# 4_shkb_downstream_power.net
KiCad netlist of a schematic drawn in Altium Designer
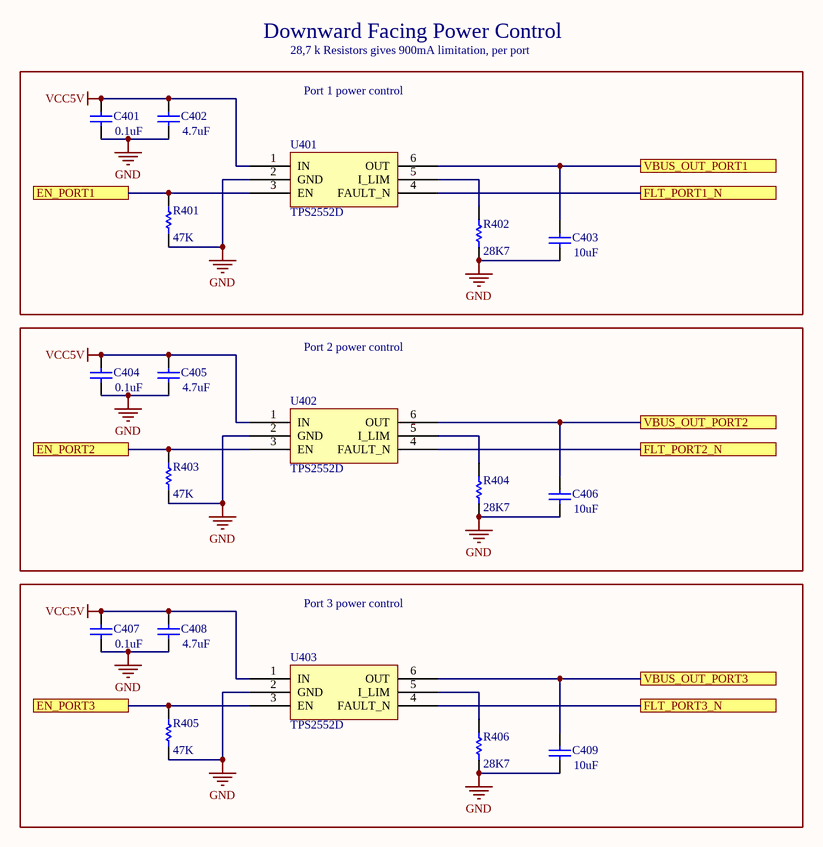
[diagram p0: 4_shkb_downstream_power.SchDoc]

(export (version "E")
  (design (tool "Eeschema 10.0.6"))
  (components
    (comp (ref "C401")
      (value "0.1uF")
      (footprint "C0603[1608]")
      (description "Capacitor")
      (fields (field (name "MFG") "KEMET") (field (name "LCSC PART #") "C14663"))
      (libsource (lib "Miscellaneous Devices") (part "Cap"))
    )
    (comp (ref "C402")
      (value "4.7uF")
      (footprint "C1206[3216]")
      (description "Capacitor")
      (fields (field (name "MFG") "KEMET") (field (name "LCSC PART #") "C29823"))
      (libsource (lib "Miscellaneous Devices") (part "Cap"))
    )
    (comp (ref "C403")
      (value "10uF")
      (footprint "C1206[3216]")
      (description "Capacitor")
      (fields (field (name "MFG") "KEMET") (field (name "LCSC PART #") "C13585"))
      (libsource (lib "Miscellaneous Devices") (part "Cap"))
    )
    (comp (ref "C404")
      (value "0.1uF")
      (footprint "C0603[1608]")
      (description "Capacitor")
      (fields (field (name "MFG") "KEMET") (field (name "LCSC PART #") "C14663"))
      (libsource (lib "Miscellaneous Devices") (part "Cap"))
    )
    (comp (ref "C405")
      (value "4.7uF")
      (footprint "C1206[3216]")
      (description "Capacitor")
      (fields (field (name "MFG") "KEMET") (field (name "LCSC PART #") "C29823"))
      (libsource (lib "Miscellaneous Devices") (part "Cap"))
    )
    (comp (ref "C406")
      (value "10uF")
      (footprint "C1206[3216]")
      (description "Capacitor")
      (fields (field (name "MFG") "KEMET") (field (name "LCSC PART #") "C13585"))
      (libsource (lib "Miscellaneous Devices") (part "Cap"))
    )
    (comp (ref "C407")
      (value "0.1uF")
      (footprint "C0603[1608]")
      (description "Capacitor")
      (fields (field (name "MFG") "KEMET") (field (name "LCSC PART #") "C14663"))
      (libsource (lib "Miscellaneous Devices") (part "Cap"))
    )
    (comp (ref "C408")
      (value "4.7uF")
      (footprint "C1206[3216]")
      (description "Capacitor")
      (fields (field (name "MFG") "KEMET") (field (name "LCSC PART #") "C29823"))
      (libsource (lib "Miscellaneous Devices") (part "Cap"))
    )
    (comp (ref "C409")
      (value "10uF")
      (footprint "C1206[3216]")
      (description "Capacitor")
      (fields (field (name "MFG") "KEMET") (field (name "LCSC PART #") "C13585"))
      (libsource (lib "Miscellaneous Devices") (part "Cap"))
    )
    (comp (ref "R401")
      (value "47K")
      (footprint "R0603[1608]")
      (description "Resistor")
      (fields (field (name "MFG") "Vishay Dale") (field (name "LCSC PART #") "C25819"))
      (libsource (lib "Miscellaneous Devices") (part "Res1"))
    )
    (comp (ref "R402")
      (value "28K7")
      (footprint "R0603[1608]")
      (description "Resistor")
      (fields (field (name "LCSC PART #") "C491124") (field (name "MRF.PART") "ERA3AEB2872V"))
      (libsource (lib "Miscellaneous Devices") (part "Res1"))
    )
    (comp (ref "R403")
      (value "47K")
      (footprint "R0603[1608]")
      (description "Resistor")
      (fields (field (name "MFG") "Vishay Dale") (field (name "LCSC PART #") "C25819"))
      (libsource (lib "Miscellaneous Devices") (part "Res1"))
    )
    (comp (ref "R404")
      (value "28K7")
      (footprint "R0603[1608]")
      (description "Resistor")
      (fields (field (name "LCSC PART #") "C491124") (field (name "MRF.PART") "ERA3AEB2872V"))
      (libsource (lib "Miscellaneous Devices") (part "Res1"))
    )
    (comp (ref "R405")
      (value "47K")
      (footprint "R0603[1608]")
      (description "Resistor")
      (fields (field (name "MFG") "Vishay Dale") (field (name "LCSC PART #") "C25819"))
      (libsource (lib "Miscellaneous Devices") (part "Res1"))
    )
    (comp (ref "R406")
      (value "28K7")
      (footprint "R0603[1608]")
      (description "Resistor")
      (fields (field (name "LCSC PART #") "C491124") (field (name "MRF.PART") "ERA3AEB2872V"))
      (libsource (lib "Miscellaneous Devices") (part "Res1"))
    )
    (comp (ref "U401")
      (value "TPS2552D")
      (footprint "SOT-23-6")
      (fields (field (name "LCSC PART #") "C140331") (field (name "MRF.PART") "TPS2552DBVR-1"))
      (libsource (lib "lib") (part "TPS2552D"))
    )
    (comp (ref "U402")
      (value "TPS2552D")
      (footprint "SOT-23-6")
      (fields (field (name "LCSC PART #") "C140331") (field (name "MRF.PART") "TPS2552DBVR-1"))
      (libsource (lib "lib") (part "TPS2552D"))
    )
    (comp (ref "U403")
      (value "TPS2552D")
      (footprint "SOT-23-6")
      (fields (field (name "LCSC PART #") "C140331") (field (name "MRF.PART") "TPS2552DBVR-1"))
      (libsource (lib "lib") (part "TPS2552D"))
    )
  )
  (nets
    (net (code "1") (name "/EN_PORT1") (class "Default")
      (node (ref "R401") (pin "1") (pinfunction "1_1") (pintype "passive"))
      (node (ref "U401") (pin "3") (pinfunction "EN_3") (pintype "passive"))
    )
    (net (code "2") (name "/EN_PORT2") (class "Default")
      (node (ref "R403") (pin "1") (pinfunction "1_1") (pintype "passive"))
      (node (ref "U402") (pin "3") (pinfunction "EN_3") (pintype "passive"))
    )
    (net (code "3") (name "/EN_PORT3") (class "Default")
      (node (ref "R405") (pin "1") (pinfunction "1_1") (pintype "passive"))
      (node (ref "U403") (pin "3") (pinfunction "EN_3") (pintype "passive"))
    )
    (net (code "4") (name "/FLT_PORT1_N") (class "Default")
      (node (ref "U401") (pin "4") (pinfunction "FAULT_N_4") (pintype "passive"))
    )
    (net (code "5") (name "/FLT_PORT2_N") (class "Default")
      (node (ref "U402") (pin "4") (pinfunction "FAULT_N_4") (pintype "passive"))
    )
    (net (code "6") (name "/FLT_PORT3_N") (class "Default")
      (node (ref "U403") (pin "4") (pinfunction "FAULT_N_4") (pintype "passive"))
    )
    (net (code "7") (name "/VBUS_OUT_PORT1") (class "Default")
      (node (ref "C403") (pin "2") (pinfunction "2_2") (pintype "passive"))
      (node (ref "U401") (pin "6") (pinfunction "OUT_6") (pintype "passive"))
    )
    (net (code "8") (name "/VBUS_OUT_PORT2") (class "Default")
      (node (ref "C406") (pin "2") (pinfunction "2_2") (pintype "passive"))
      (node (ref "U402") (pin "6") (pinfunction "OUT_6") (pintype "passive"))
    )
    (net (code "9") (name "/VBUS_OUT_PORT3") (class "Default")
      (node (ref "C409") (pin "2") (pinfunction "2_2") (pintype "passive"))
      (node (ref "U403") (pin "6") (pinfunction "OUT_6") (pintype "passive"))
    )
    (net (code "10") (name "GND") (class "Default")
      (node (ref "C401") (pin "1") (pinfunction "1_1") (pintype "passive"))
      (node (ref "C402") (pin "1") (pinfunction "1_1") (pintype "passive"))
      (node (ref "C403") (pin "1") (pinfunction "1_1") (pintype "passive"))
      (node (ref "C404") (pin "1") (pinfunction "1_1") (pintype "passive"))
      (node (ref "C405") (pin "1") (pinfunction "1_1") (pintype "passive"))
      (node (ref "C406") (pin "1") (pinfunction "1_1") (pintype "passive"))
      (node (ref "C407") (pin "1") (pinfunction "1_1") (pintype "passive"))
      (node (ref "C408") (pin "1") (pinfunction "1_1") (pintype "passive"))
      (node (ref "C409") (pin "1") (pinfunction "1_1") (pintype "passive"))
      (node (ref "R401") (pin "2") (pinfunction "2_2") (pintype "passive"))
      (node (ref "R402") (pin "2") (pinfunction "2_2") (pintype "passive"))
      (node (ref "R403") (pin "2") (pinfunction "2_2") (pintype "passive"))
      (node (ref "R404") (pin "2") (pinfunction "2_2") (pintype "passive"))
      (node (ref "R405") (pin "2") (pinfunction "2_2") (pintype "passive"))
      (node (ref "R406") (pin "2") (pinfunction "2_2") (pintype "passive"))
      (node (ref "U401") (pin "2") (pinfunction "GND_2") (pintype "passive"))
      (node (ref "U402") (pin "2") (pinfunction "GND_2") (pintype "passive"))
      (node (ref "U403") (pin "2") (pinfunction "GND_2") (pintype "passive"))
    )
    (net (code "11") (name "Net-(U401-I_LIM)") (class "Default")
      (node (ref "R402") (pin "1") (pinfunction "1_1") (pintype "passive"))
      (node (ref "U401") (pin "5") (pinfunction "I_LIM_5") (pintype "passive"))
    )
    (net (code "12") (name "Net-(U402-I_LIM)") (class "Default")
      (node (ref "R404") (pin "1") (pinfunction "1_1") (pintype "passive"))
      (node (ref "U402") (pin "5") (pinfunction "I_LIM_5") (pintype "passive"))
    )
    (net (code "13") (name "Net-(U403-I_LIM)") (class "Default")
      (node (ref "R406") (pin "1") (pinfunction "1_1") (pintype "passive"))
      (node (ref "U403") (pin "5") (pinfunction "I_LIM_5") (pintype "passive"))
    )
    (net (code "14") (name "VCC5V") (class "Default")
      (node (ref "C401") (pin "2") (pinfunction "2_2") (pintype "passive"))
      (node (ref "C402") (pin "2") (pinfunction "2_2") (pintype "passive"))
      (node (ref "C404") (pin "2") (pinfunction "2_2") (pintype "passive"))
      (node (ref "C405") (pin "2") (pinfunction "2_2") (pintype "passive"))
      (node (ref "C407") (pin "2") (pinfunction "2_2") (pintype "passive"))
      (node (ref "C408") (pin "2") (pinfunction "2_2") (pintype "passive"))
      (node (ref "U401") (pin "1") (pinfunction "IN_1") (pintype "passive"))
      (node (ref "U402") (pin "1") (pinfunction "IN_1") (pintype "passive"))
      (node (ref "U403") (pin "1") (pinfunction "IN_1") (pintype "passive"))
    )
  )
)
